# FiltroAntialiasing.net
KiCad netlist of a schematic drawn in Altium Designer
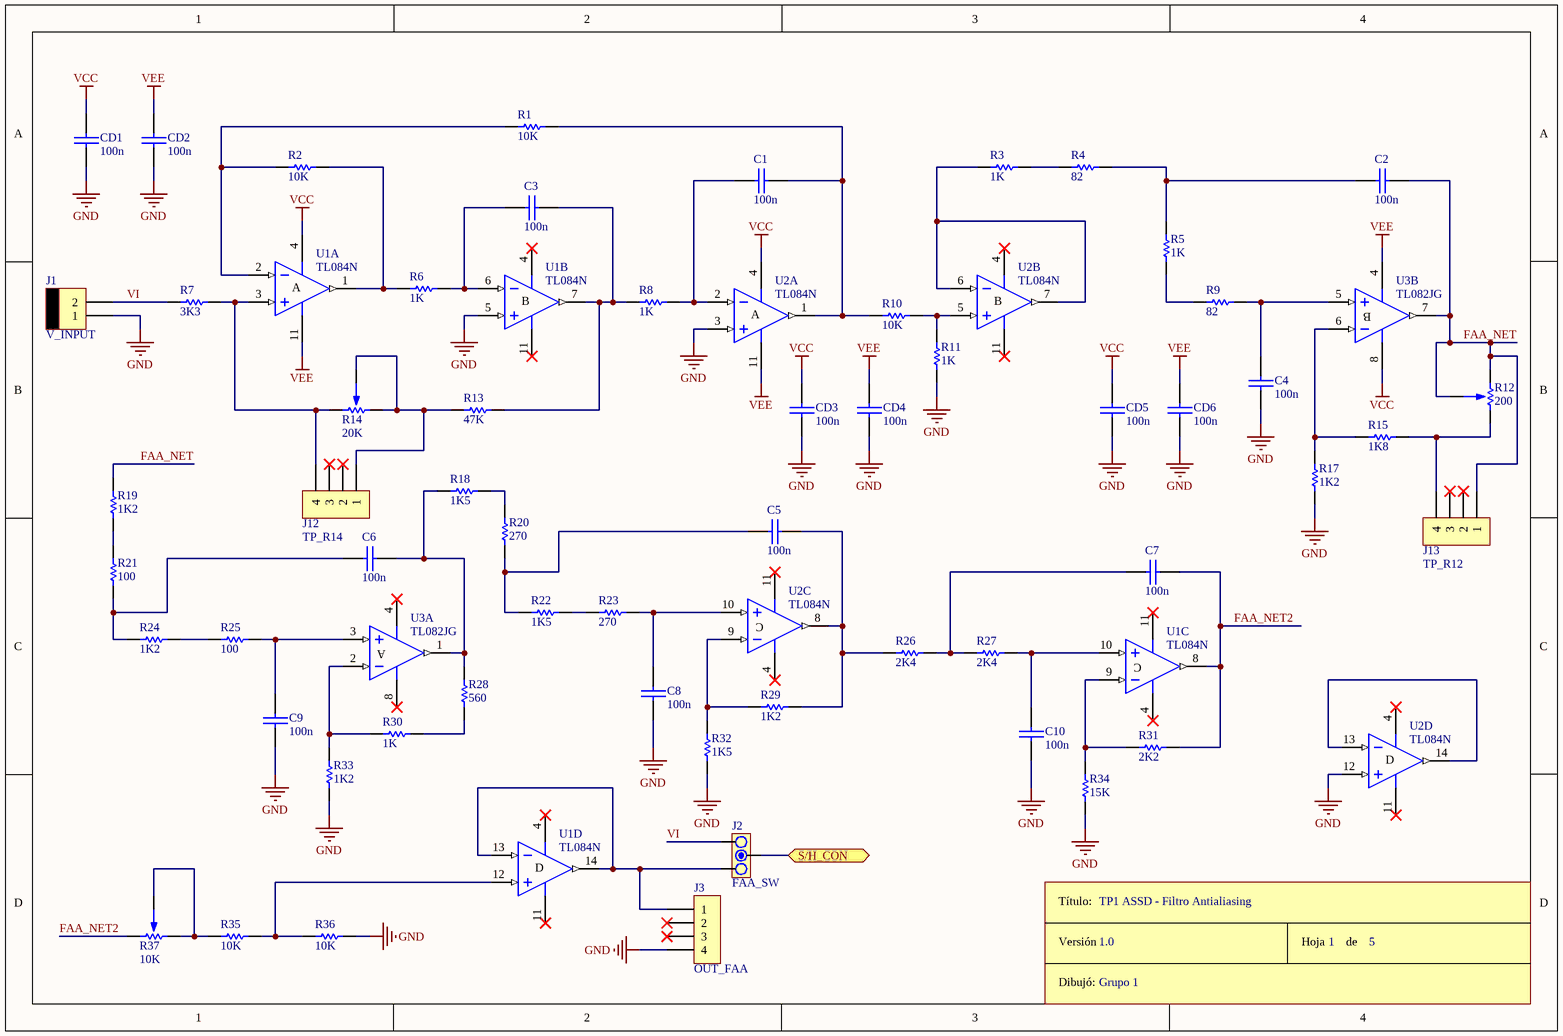
[diagram p0: FiltroAntialiasing.SchDoc]

(export (version "E")
  (design (tool "Eeschema 10.0.6"))
  (components
    (comp (ref "C1") (value "100n") (footprint "CAP100") (libsource (lib "LIBEBAL") (part "CAP")))
    (comp (ref "C2") (value "100n") (footprint "CAP100") (libsource (lib "LIBEBAL") (part "CAP")))
    (comp (ref "C3") (value "100n") (footprint "CAP100") (libsource (lib "LIBEBAL") (part "CAP")))
    (comp (ref "C4") (value "100n") (footprint "CAP100") (libsource (lib "LIBEBAL") (part "CAP")))
    (comp (ref "C5") (value "100n") (footprint "CAP100") (libsource (lib "LIBEBAL") (part "CAP")))
    (comp (ref "C6") (value "100n") (footprint "CAP100") (libsource (lib "LIBEBAL") (part "CAP")))
    (comp (ref "C7") (value "100n") (footprint "CAP100") (libsource (lib "LIBEBAL") (part "CAP")))
    (comp (ref "C8") (value "100n") (footprint "CAP100") (libsource (lib "LIBEBAL") (part "CAP")))
    (comp (ref "C9") (value "100n") (footprint "CAP100") (libsource (lib "LIBEBAL") (part "CAP")))
    (comp (ref "C10") (value "100n") (footprint "CAP100") (libsource (lib "LIBEBAL") (part "CAP")))
    (comp (ref "CD1") (value "100n") (footprint "CAP100") (libsource (lib "LIBEBAL") (part "CAP")))
    (comp (ref "CD2") (value "100n") (footprint "CAP100") (libsource (lib "LIBEBAL") (part "CAP")))
    (comp (ref "CD3") (value "100n") (footprint "CAP100") (libsource (lib "LIBEBAL") (part "CAP")))
    (comp (ref "CD4") (value "100n") (footprint "CAP100") (libsource (lib "LIBEBAL") (part "CAP")))
    (comp (ref "CD5") (value "100n") (footprint "CAP100") (libsource (lib "LIBEBAL") (part "CAP")))
    (comp (ref "CD6") (value "100n") (footprint "CAP100") (libsource (lib "LIBEBAL") (part "CAP")))
    (comp (ref "J1") (value "V_INPUT") (footprint "MOLEX2") (libsource (lib "LIBEBAL") (part "MOLEX2")))
    (comp (ref "J2") (value "FAA_SW") (footprint "JUMPER3") (libsource (lib "LIBEBAL") (part "JUMPER3")))
    (comp (ref "J3") (value "OUT_FAA") (footprint "SIP4") (libsource (lib "LIBEBAL") (part "CON4")))
    (comp (ref "J12") (value "TP_R14") (footprint "SIP4") (libsource (lib "") (part "CON4_1")))
    (comp (ref "J13") (value "TP_R12") (footprint "SIP4") (libsource (lib "") (part "CON4_1")))
    (comp (ref "R1") (value "10K") (footprint "RES400") (libsource (lib "LIBEBAL") (part "RES")))
    (comp (ref "R2") (value "10K") (footprint "RES400") (libsource (lib "LIBEBAL") (part "RES")))
    (comp (ref "R3") (value "1K") (footprint "RES400") (libsource (lib "LIBEBAL") (part "RES")))
    (comp (ref "R4") (value "82") (footprint "RES400") (libsource (lib "LIBEBAL") (part "RES")))
    (comp (ref "R5") (value "1K") (footprint "RES400") (libsource (lib "LIBEBAL") (part "RES")))
    (comp (ref "R6") (value "1K") (footprint "RES400") (libsource (lib "LIBEBAL") (part "RES")))
    (comp (ref "R7") (value "3K3") (footprint "RES400") (libsource (lib "LIBEBAL") (part "RES")))
    (comp (ref "R8") (value "1K") (footprint "RES400") (libsource (lib "LIBEBAL") (part "RES")))
    (comp (ref "R9") (value "82") (footprint "RES400") (libsource (lib "LIBEBAL") (part "RES")))
    (comp (ref "R10") (value "10K") (footprint "RES400") (libsource (lib "LIBEBAL") (part "RES")))
    (comp (ref "R11") (value "1K") (footprint "RES400") (libsource (lib "LIBEBAL") (part "RES")))
    (comp (ref "R12") (value "200") (footprint "PRESET V") (libsource (lib "LIBEBAL") (part "PRESET")))
    (comp (ref "R13") (value "47K") (footprint "RES400") (libsource (lib "LIBEBAL") (part "RES")))
    (comp (ref "R14") (value "20K") (footprint "PRESET V") (libsource (lib "LIBEBAL") (part "PRESET")))
    (comp (ref "R15") (value "1K8") (footprint "RES400") (libsource (lib "LIBEBAL") (part "RES")))
    (comp (ref "R17") (value "1K2") (footprint "RES400") (libsource (lib "LIBEBAL") (part "RES")))
    (comp (ref "R18") (value "1K5") (footprint "RES400") (libsource (lib "LIBEBAL") (part "RES")))
    (comp (ref "R19") (value "1K2") (footprint "RES400") (libsource (lib "LIBEBAL") (part "RES")))
    (comp (ref "R20") (value "270") (footprint "RES400") (libsource (lib "LIBEBAL") (part "RES")))
    (comp (ref "R21") (value "100") (footprint "RES400") (libsource (lib "LIBEBAL") (part "RES")))
    (comp (ref "R22") (value "1K5") (footprint "RES400") (libsource (lib "LIBEBAL") (part "RES")))
    (comp (ref "R23") (value "270") (footprint "RES400") (libsource (lib "LIBEBAL") (part "RES")))
    (comp (ref "R24") (value "1K2") (footprint "RES400") (libsource (lib "LIBEBAL") (part "RES")))
    (comp (ref "R25") (value "100") (footprint "RES400") (libsource (lib "LIBEBAL") (part "RES")))
    (comp (ref "R26") (value "2K4") (footprint "RES400") (libsource (lib "LIBEBAL") (part "RES")))
    (comp (ref "R27") (value "2K4") (footprint "RES400") (libsource (lib "LIBEBAL") (part "RES")))
    (comp (ref "R28") (value "560") (footprint "RES400") (libsource (lib "LIBEBAL") (part "RES")))
    (comp (ref "R29") (value "1K2") (footprint "RES400") (libsource (lib "LIBEBAL") (part "RES")))
    (comp (ref "R30") (value "1K") (footprint "RES400") (libsource (lib "LIBEBAL") (part "RES")))
    (comp (ref "R31") (value "2K2") (footprint "RES400") (libsource (lib "LIBEBAL") (part "RES")))
    (comp (ref "R32") (value "1K5") (footprint "RES400") (libsource (lib "LIBEBAL") (part "RES")))
    (comp (ref "R33") (value "1K2") (footprint "RES400") (libsource (lib "LIBEBAL") (part "RES")))
    (comp (ref "R34") (value "15K") (footprint "RES400") (libsource (lib "LIBEBAL") (part "RES")))
    (comp (ref "R35") (value "10K") (footprint "RES400") (libsource (lib "LIBEBAL") (part "RES")))
    (comp (ref "R36") (value "10K") (footprint "RES400") (libsource (lib "LIBEBAL") (part "RES")))
    (comp (ref "R37") (value "10K") (footprint "PRESET V") (libsource (lib "LIBEBAL") (part "PRESET")))
    (comp (ref "ROT1") (value "Rótulo") (libsource (lib "LIB PIO IX") (part "Rótulo")))
    (comp (ref "U1")
      (value "TL084N")
      (footprint "N014")
      (description "JFET-Input Operational Amplifier")
      (fields (field (name "PUBLISHER") "Altium Limited"))
      (libsource (lib "TI Operational Amplifier") (part "TL084N"))
    )
    (comp (ref "U2")
      (value "TL084N")
      (footprint "N014")
      (description "JFET-Input Operational Amplifier")
      (fields (field (name "PUBLISHER") "Altium Limited"))
      (libsource (lib "TI Operational Amplifier") (part "TL084N"))
    )
    (comp (ref "U3")
      (value "TL082JG")
      (footprint "JG008")
      (description "JFET-Input Operational Amplifier")
      (fields (field (name "PUBLISHER") "Altium Limited"))
      (libsource (lib "TI Operational Amplifier") (part "TL082JG"))
    )
  )
  (nets
    (net (code "1") (name "/FAA_NET") (class "Default")
      (node (ref "C2") (pin "2") (pinfunction "2_2") (pintype "passive"))
      (node (ref "J13") (pin "1") (pinfunction "1_1") (pintype "passive"))
      (node (ref "R12") (pin "2") (pinfunction "2_2") (pintype "passive"))
      (node (ref "R12") (pin "3") (pinfunction "3_3") (pintype "passive"))
      (node (ref "R19") (pin "1") (pinfunction "1_1") (pintype "passive"))
      (node (ref "U3") (pin "7") (pinfunction "OUT_7") (pintype "output"))
    )
    (net (code "2") (name "/FAA_NET2") (class "Default")
      (node (ref "C7") (pin "2") (pinfunction "2_2") (pintype "passive"))
      (node (ref "R31") (pin "2") (pinfunction "2_2") (pintype "passive"))
      (node (ref "R37") (pin "1") (pinfunction "1_1") (pintype "passive"))
      (node (ref "U1") (pin "8") (pinfunction "OUT_8") (pintype "output"))
    )
    (net (code "3") (name "/S{slash}H_CON") (class "Default")
      (node (ref "J2") (pin "2") (pinfunction "2_2") (pintype "passive"))
    )
    (net (code "4") (name "/VI") (class "Default")
      (node (ref "J1") (pin "2") (pinfunction "2_2") (pintype "passive"))
      (node (ref "J2") (pin "3") (pinfunction "3_3") (pintype "passive"))
      (node (ref "R7") (pin "1") (pinfunction "1_1") (pintype "passive"))
    )
    (net (code "5") (name "GND") (class "Default")
      (node (ref "C10") (pin "2") (pinfunction "2_2") (pintype "passive"))
      (node (ref "C4") (pin "2") (pinfunction "2_2") (pintype "passive"))
      (node (ref "C8") (pin "2") (pinfunction "2_2") (pintype "passive"))
      (node (ref "C9") (pin "1") (pinfunction "1_1") (pintype "passive"))
      (node (ref "CD1") (pin "2") (pinfunction "2_2") (pintype "passive"))
      (node (ref "CD2") (pin "2") (pinfunction "2_2") (pintype "passive"))
      (node (ref "CD3") (pin "2") (pinfunction "2_2") (pintype "passive"))
      (node (ref "CD4") (pin "2") (pinfunction "2_2") (pintype "passive"))
      (node (ref "CD5") (pin "2") (pinfunction "2_2") (pintype "passive"))
      (node (ref "CD6") (pin "2") (pinfunction "2_2") (pintype "passive"))
      (node (ref "J1") (pin "1") (pinfunction "1_1") (pintype "passive"))
      (node (ref "J3") (pin "4") (pinfunction "4_4") (pintype "passive"))
      (node (ref "R11") (pin "1") (pinfunction "1_1") (pintype "passive"))
      (node (ref "R17") (pin "1") (pinfunction "1_1") (pintype "passive"))
      (node (ref "R32") (pin "1") (pinfunction "1_1") (pintype "passive"))
      (node (ref "R33") (pin "1") (pinfunction "1_1") (pintype "passive"))
      (node (ref "R34") (pin "1") (pinfunction "1_1") (pintype "passive"))
      (node (ref "R36") (pin "1") (pinfunction "1_1") (pintype "passive"))
      (node (ref "U1") (pin "5") (pinfunction "IN+_5") (pintype "input"))
      (node (ref "U2") (pin "12") (pinfunction "IN+_12") (pintype "input"))
      (node (ref "U2") (pin "3") (pinfunction "IN+_3") (pintype "input"))
    )
    (net (code "6") (name "Net-(C2-Pad1)") (class "Default")
      (node (ref "C2") (pin "1") (pinfunction "1_1") (pintype "passive"))
      (node (ref "R4") (pin "2") (pinfunction "2_2") (pintype "passive"))
      (node (ref "R5") (pin "2") (pinfunction "2_2") (pintype "passive"))
    )
    (net (code "7") (name "Net-(C5-Pad1)") (class "Default")
      (node (ref "C5") (pin "1") (pinfunction "1_1") (pintype "passive"))
      (node (ref "R20") (pin "2") (pinfunction "2_2") (pintype "passive"))
      (node (ref "R22") (pin "1") (pinfunction "1_1") (pintype "passive"))
    )
    (net (code "8") (name "Net-(C6-Pad1)") (class "Default")
      (node (ref "C6") (pin "1") (pinfunction "1_1") (pintype "passive"))
      (node (ref "R21") (pin "2") (pinfunction "2_2") (pintype "passive"))
      (node (ref "R24") (pin "1") (pinfunction "1_1") (pintype "passive"))
    )
    (net (code "9") (name "Net-(C7-Pad1)") (class "Default")
      (node (ref "C7") (pin "1") (pinfunction "1_1") (pintype "passive"))
      (node (ref "R26") (pin "2") (pinfunction "2_2") (pintype "passive"))
      (node (ref "R27") (pin "1") (pinfunction "1_1") (pintype "passive"))
    )
    (net (code "10") (name "Net-(J12-Pad1)") (class "Default")
      (node (ref "J12") (pin "1") (pinfunction "1_1") (pintype "passive"))
      (node (ref "R13") (pin "1") (pinfunction "1_1") (pintype "passive"))
      (node (ref "R14") (pin "2") (pinfunction "2_2") (pintype "passive"))
      (node (ref "R14") (pin "3") (pinfunction "3_3") (pintype "passive"))
    )
    (net (code "11") (name "Net-(J13-Pad4)") (class "Default")
      (node (ref "J13") (pin "4") (pinfunction "4_4") (pintype "passive"))
      (node (ref "R12") (pin "1") (pinfunction "1_1") (pintype "passive"))
      (node (ref "R15") (pin "2") (pinfunction "2_2") (pintype "passive"))
    )
    (net (code "12") (name "Net-(R3-Pad1)") (class "Default")
      (node (ref "R3") (pin "1") (pinfunction "1_1") (pintype "passive"))
      (node (ref "R4") (pin "1") (pinfunction "1_1") (pintype "passive"))
    )
    (net (code "13") (name "Net-(R5-Pad1)") (class "Default")
      (node (ref "R5") (pin "1") (pinfunction "1_1") (pintype "passive"))
      (node (ref "R9") (pin "1") (pinfunction "1_1") (pintype "passive"))
    )
    (net (code "14") (name "Net-(R18-Pad1)") (class "Default")
      (node (ref "R18") (pin "1") (pinfunction "1_1") (pintype "passive"))
      (node (ref "R20") (pin "1") (pinfunction "1_1") (pintype "passive"))
    )
    (net (code "15") (name "Net-(R19-Pad2)") (class "Default")
      (node (ref "R19") (pin "2") (pinfunction "2_2") (pintype "passive"))
      (node (ref "R21") (pin "1") (pinfunction "1_1") (pintype "passive"))
    )
    (net (code "16") (name "Net-(R22-Pad2)") (class "Default")
      (node (ref "R22") (pin "2") (pinfunction "2_2") (pintype "passive"))
      (node (ref "R23") (pin "1") (pinfunction "1_1") (pintype "passive"))
    )
    (net (code "17") (name "Net-(R24-Pad2)") (class "Default")
      (node (ref "R24") (pin "2") (pinfunction "2_2") (pintype "passive"))
      (node (ref "R25") (pin "1") (pinfunction "1_1") (pintype "passive"))
    )
    (net (code "18") (name "Net-(R28-Pad1)") (class "Default")
      (node (ref "R28") (pin "1") (pinfunction "1_1") (pintype "passive"))
      (node (ref "R30") (pin "2") (pinfunction "2_2") (pintype "passive"))
    )
    (net (code "19") (name "Net-(R35-Pad1)") (class "Default")
      (node (ref "R35") (pin "1") (pinfunction "1_1") (pintype "passive"))
      (node (ref "R37") (pin "2") (pinfunction "2_2") (pintype "passive"))
      (node (ref "R37") (pin "3") (pinfunction "3_3") (pintype "passive"))
    )
    (net (code "20") (name "Net-(U1A-IN+)") (class "Default")
      (node (ref "J12") (pin "4") (pinfunction "4_4") (pintype "passive"))
      (node (ref "R14") (pin "1") (pinfunction "1_1") (pintype "passive"))
      (node (ref "R7") (pin "2") (pinfunction "2_2") (pintype "passive"))
      (node (ref "U1") (pin "3") (pinfunction "IN+_3") (pintype "input"))
    )
    (net (code "21") (name "Net-(U1A-IN-)") (class "Default")
      (node (ref "R1") (pin "1") (pinfunction "1_1") (pintype "passive"))
      (node (ref "R2") (pin "1") (pinfunction "1_1") (pintype "passive"))
      (node (ref "U1") (pin "2") (pinfunction "IN-_2") (pintype "input"))
    )
    (net (code "22") (name "Net-(U1A-OUT)") (class "Default")
      (node (ref "R2") (pin "2") (pinfunction "2_2") (pintype "passive"))
      (node (ref "R6") (pin "1") (pinfunction "1_1") (pintype "passive"))
      (node (ref "U1") (pin "1") (pinfunction "OUT_1") (pintype "output"))
    )
    (net (code "23") (name "Net-(U1B-IN-)") (class "Default")
      (node (ref "C3") (pin "1") (pinfunction "1_1") (pintype "passive"))
      (node (ref "R6") (pin "2") (pinfunction "2_2") (pintype "passive"))
      (node (ref "U1") (pin "6") (pinfunction "IN-_6") (pintype "input"))
    )
    (net (code "24") (name "Net-(U1B-OUT)") (class "Default")
      (node (ref "C3") (pin "2") (pinfunction "2_2") (pintype "passive"))
      (node (ref "R13") (pin "2") (pinfunction "2_2") (pintype "passive"))
      (node (ref "R8") (pin "1") (pinfunction "1_1") (pintype "passive"))
      (node (ref "U1") (pin "7") (pinfunction "OUT_7") (pintype "output"))
    )
    (net (code "25") (name "Net-(U1C-IN+)") (class "Default")
      (node (ref "C10") (pin "1") (pinfunction "1_1") (pintype "passive"))
      (node (ref "R27") (pin "2") (pinfunction "2_2") (pintype "passive"))
      (node (ref "U1") (pin "10") (pinfunction "IN+_10") (pintype "input"))
    )
    (net (code "26") (name "Net-(U1C-IN-)") (class "Default")
      (node (ref "R31") (pin "1") (pinfunction "1_1") (pintype "passive"))
      (node (ref "R34") (pin "2") (pinfunction "2_2") (pintype "passive"))
      (node (ref "U1") (pin "9") (pinfunction "IN-_9") (pintype "input"))
    )
    (net (code "27") (name "Net-(U1D-IN+)") (class "Default")
      (node (ref "R35") (pin "2") (pinfunction "2_2") (pintype "passive"))
      (node (ref "R36") (pin "2") (pinfunction "2_2") (pintype "passive"))
      (node (ref "U1") (pin "12") (pinfunction "IN+_12") (pintype "input"))
    )
    (net (code "28") (name "Net-(U1D-IN-)") (class "Default")
      (node (ref "J2") (pin "1") (pinfunction "1_1") (pintype "passive"))
      (node (ref "J3") (pin "1") (pinfunction "1_1") (pintype "passive"))
      (node (ref "U1") (pin "13") (pinfunction "IN-_13") (pintype "input"))
      (node (ref "U1") (pin "14") (pinfunction "OUT_14") (pintype "output"))
    )
    (net (code "29") (name "Net-(U2A-IN-)") (class "Default")
      (node (ref "C1") (pin "1") (pinfunction "1_1") (pintype "passive"))
      (node (ref "R8") (pin "2") (pinfunction "2_2") (pintype "passive"))
      (node (ref "U2") (pin "2") (pinfunction "IN-_2") (pintype "input"))
    )
    (net (code "30") (name "Net-(U2A-OUT)") (class "Default")
      (node (ref "C1") (pin "2") (pinfunction "2_2") (pintype "passive"))
      (node (ref "R1") (pin "2") (pinfunction "2_2") (pintype "passive"))
      (node (ref "R10") (pin "1") (pinfunction "1_1") (pintype "passive"))
      (node (ref "U2") (pin "1") (pinfunction "OUT_1") (pintype "output"))
    )
    (net (code "31") (name "Net-(U2B-IN+)") (class "Default")
      (node (ref "R10") (pin "2") (pinfunction "2_2") (pintype "passive"))
      (node (ref "R11") (pin "2") (pinfunction "2_2") (pintype "passive"))
      (node (ref "U2") (pin "5") (pinfunction "IN+_5") (pintype "input"))
    )
    (net (code "32") (name "Net-(U2B-IN-)") (class "Default")
      (node (ref "R3") (pin "2") (pinfunction "2_2") (pintype "passive"))
      (node (ref "U2") (pin "6") (pinfunction "IN-_6") (pintype "input"))
      (node (ref "U2") (pin "7") (pinfunction "OUT_7") (pintype "output"))
    )
    (net (code "33") (name "Net-(U2C-IN+)") (class "Default")
      (node (ref "C8") (pin "1") (pinfunction "1_1") (pintype "passive"))
      (node (ref "R23") (pin "2") (pinfunction "2_2") (pintype "passive"))
      (node (ref "U2") (pin "10") (pinfunction "IN+_10") (pintype "input"))
    )
    (net (code "34") (name "Net-(U2C-IN-)") (class "Default")
      (node (ref "R29") (pin "1") (pinfunction "1_1") (pintype "passive"))
      (node (ref "R32") (pin "2") (pinfunction "2_2") (pintype "passive"))
      (node (ref "U2") (pin "9") (pinfunction "IN-_9") (pintype "input"))
    )
    (net (code "35") (name "Net-(U2C-OUT)") (class "Default")
      (node (ref "C5") (pin "2") (pinfunction "2_2") (pintype "passive"))
      (node (ref "R26") (pin "1") (pinfunction "1_1") (pintype "passive"))
      (node (ref "R29") (pin "2") (pinfunction "2_2") (pintype "passive"))
      (node (ref "U2") (pin "8") (pinfunction "OUT_8") (pintype "output"))
    )
    (net (code "36") (name "Net-(U2D-IN-)") (class "Default")
      (node (ref "U2") (pin "13") (pinfunction "IN-_13") (pintype "input"))
      (node (ref "U2") (pin "14") (pinfunction "OUT_14") (pintype "output"))
    )
    (net (code "37") (name "Net-(U3A-IN+)") (class "Default")
      (node (ref "C9") (pin "2") (pinfunction "2_2") (pintype "passive"))
      (node (ref "R25") (pin "2") (pinfunction "2_2") (pintype "passive"))
      (node (ref "U3") (pin "3") (pinfunction "IN+_3") (pintype "input"))
    )
    (net (code "38") (name "Net-(U3A-IN-)") (class "Default")
      (node (ref "R30") (pin "1") (pinfunction "1_1") (pintype "passive"))
      (node (ref "R33") (pin "2") (pinfunction "2_2") (pintype "passive"))
      (node (ref "U3") (pin "2") (pinfunction "IN-_2") (pintype "input"))
    )
    (net (code "39") (name "Net-(U3A-OUT)") (class "Default")
      (node (ref "C6") (pin "2") (pinfunction "2_2") (pintype "passive"))
      (node (ref "R18") (pin "2") (pinfunction "2_2") (pintype "passive"))
      (node (ref "R28") (pin "2") (pinfunction "2_2") (pintype "passive"))
      (node (ref "U3") (pin "1") (pinfunction "OUT_1") (pintype "output"))
    )
    (net (code "40") (name "Net-(U3B-IN+)") (class "Default")
      (node (ref "C4") (pin "1") (pinfunction "1_1") (pintype "passive"))
      (node (ref "R9") (pin "2") (pinfunction "2_2") (pintype "passive"))
      (node (ref "U3") (pin "5") (pinfunction "IN+_5") (pintype "input"))
    )
    (net (code "41") (name "Net-(U3B-IN-)") (class "Default")
      (node (ref "R15") (pin "1") (pinfunction "1_1") (pintype "passive"))
      (node (ref "R17") (pin "2") (pinfunction "2_2") (pintype "passive"))
      (node (ref "U3") (pin "6") (pinfunction "IN-_6") (pintype "input"))
    )
    (net (code "42") (name "VCC") (class "Default")
      (node (ref "CD1") (pin "1") (pinfunction "1_1") (pintype "passive"))
      (node (ref "CD3") (pin "1") (pinfunction "1_1") (pintype "passive"))
      (node (ref "CD5") (pin "1") (pinfunction "1_1") (pintype "passive"))
      (node (ref "U1") (pin "4") (pinfunction "V+_4") (pintype "power_in"))
      (node (ref "U2") (pin "4") (pinfunction "V+_4") (pintype "power_in"))
      (node (ref "U3") (pin "8") (pinfunction "V+_8") (pintype "power_in"))
    )
    (net (code "43") (name "VEE") (class "Default")
      (node (ref "CD2") (pin "1") (pinfunction "1_1") (pintype "passive"))
      (node (ref "CD4") (pin "1") (pinfunction "1_1") (pintype "passive"))
      (node (ref "CD6") (pin "1") (pinfunction "1_1") (pintype "passive"))
      (node (ref "U1") (pin "11") (pinfunction "V-_11") (pintype "power_in"))
      (node (ref "U2") (pin "11") (pinfunction "V-_11") (pintype "power_in"))
      (node (ref "U3") (pin "4") (pinfunction "V-_4") (pintype "power_in"))
    )
    (net (code "44") (name "unconnected-(J3-Pad2)") (class "Default")
      (node (ref "J3") (pin "2") (pinfunction "2_2") (pintype "passive+no_connect"))
    )
    (net (code "45") (name "unconnected-(J3-Pad3)") (class "Default")
      (node (ref "J3") (pin "3") (pinfunction "3_3") (pintype "passive+no_connect"))
    )
    (net (code "46") (name "unconnected-(J12-Pad2)") (class "Default")
      (node (ref "J12") (pin "2") (pinfunction "2_2") (pintype "passive+no_connect"))
    )
    (net (code "47") (name "unconnected-(J12-Pad3)") (class "Default")
      (node (ref "J12") (pin "3") (pinfunction "3_3") (pintype "passive+no_connect"))
    )
    (net (code "48") (name "unconnected-(J13-Pad2)") (class "Default")
      (node (ref "J13") (pin "2") (pinfunction "2_2") (pintype "passive+no_connect"))
    )
    (net (code "49") (name "unconnected-(J13-Pad3)") (class "Default")
      (node (ref "J13") (pin "3") (pinfunction "3_3") (pintype "passive+no_connect"))
    )
    (net (code "50") (name "unconnected-(U1B-V+-Pad4)") (class "Default")
      (node (ref "U1") (pin "4") (pinfunction "V+_4") (pintype "power_in+no_connect"))
    )
    (net (code "51") (name "unconnected-(U1B-V--Pad11)") (class "Default")
      (node (ref "U1") (pin "11") (pinfunction "V-_11") (pintype "power_in+no_connect"))
    )
    (net (code "52") (name "unconnected-(U1C-V+-Pad4)") (class "Default")
      (node (ref "U1") (pin "4") (pinfunction "V+_4") (pintype "power_in+no_connect"))
    )
    (net (code "53") (name "unconnected-(U1C-V--Pad11)") (class "Default")
      (node (ref "U1") (pin "11") (pinfunction "V-_11") (pintype "power_in+no_connect"))
    )
    (net (code "54") (name "unconnected-(U1D-V+-Pad4)") (class "Default")
      (node (ref "U1") (pin "4") (pinfunction "V+_4") (pintype "power_in+no_connect"))
    )
    (net (code "55") (name "unconnected-(U1D-V--Pad11)") (class "Default")
      (node (ref "U1") (pin "11") (pinfunction "V-_11") (pintype "power_in+no_connect"))
    )
    (net (code "56") (name "unconnected-(U2B-V+-Pad4)") (class "Default")
      (node (ref "U2") (pin "4") (pinfunction "V+_4") (pintype "power_in+no_connect"))
    )
    (net (code "57") (name "unconnected-(U2B-V--Pad11)") (class "Default")
      (node (ref "U2") (pin "11") (pinfunction "V-_11") (pintype "power_in+no_connect"))
    )
    (net (code "58") (name "unconnected-(U2C-V+-Pad4)") (class "Default")
      (node (ref "U2") (pin "4") (pinfunction "V+_4") (pintype "power_in+no_connect"))
    )
    (net (code "59") (name "unconnected-(U2C-V--Pad11)") (class "Default")
      (node (ref "U2") (pin "11") (pinfunction "V-_11") (pintype "power_in+no_connect"))
    )
    (net (code "60") (name "unconnected-(U2D-V+-Pad4)") (class "Default")
      (node (ref "U2") (pin "4") (pinfunction "V+_4") (pintype "power_in+no_connect"))
    )
    (net (code "61") (name "unconnected-(U2D-V--Pad11)") (class "Default")
      (node (ref "U2") (pin "11") (pinfunction "V-_11") (pintype "power_in+no_connect"))
    )
    (net (code "62") (name "unconnected-(U3A-V+-Pad8)") (class "Default")
      (node (ref "U3") (pin "8") (pinfunction "V+_8") (pintype "power_in+no_connect"))
    )
    (net (code "63") (name "unconnected-(U3A-V--Pad4)") (class "Default")
      (node (ref "U3") (pin "4") (pinfunction "V-_4") (pintype "power_in+no_connect"))
    )
  )
)
